# design.net
KiCad netlist of a schematic drawn in Altium Designer
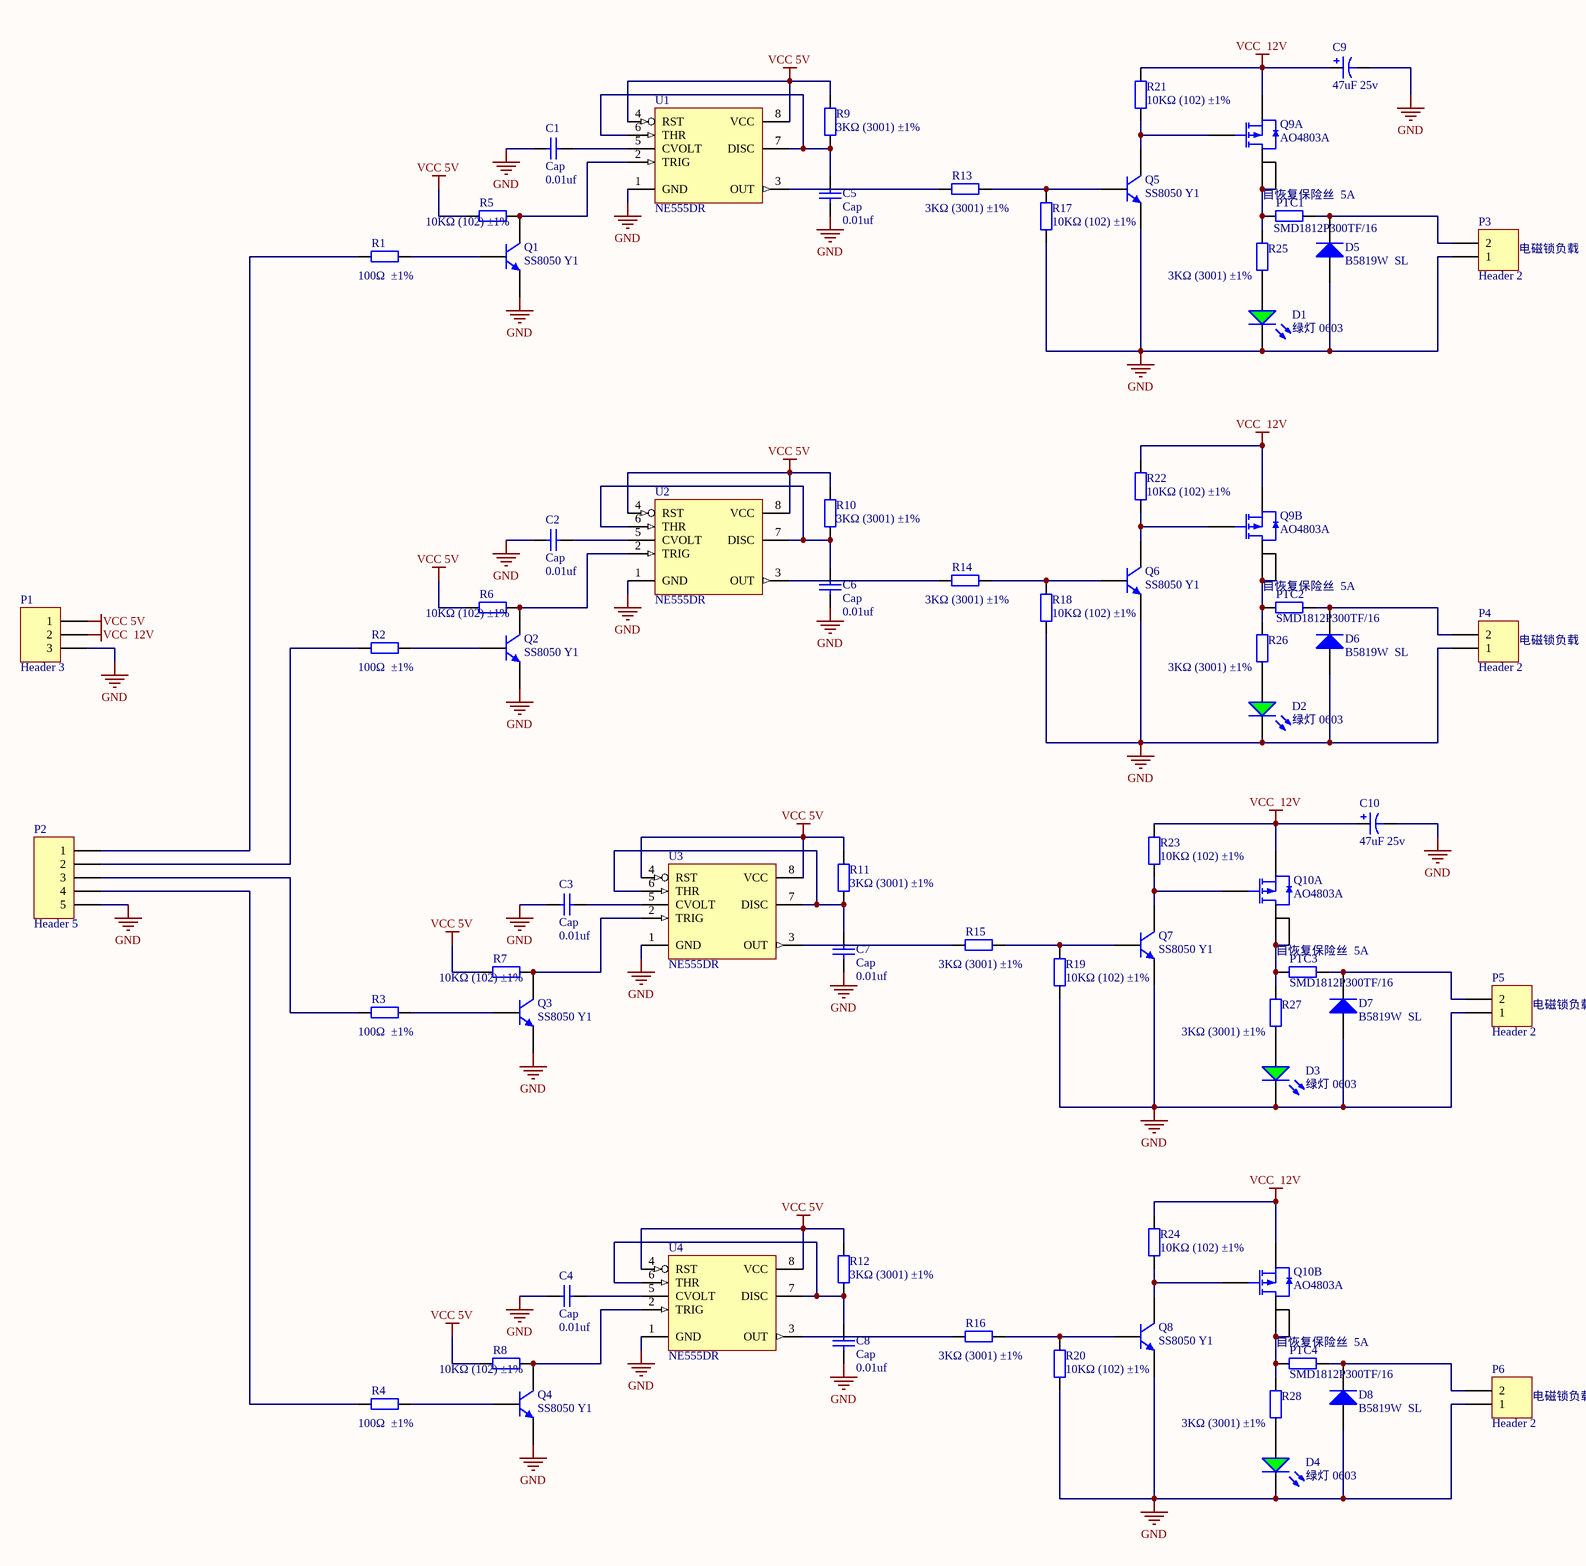
[diagram p0: 电磁阀驱动.SchDoc]

(export (version "E")
  (design (tool "Eeschema 10.0.6"))
  (components
    (comp (ref "C1")
      (value "Cap")
      (footprint "0603C")
      (description "Capacitor")
      (fields (field (name "ALTIUM_VALUE") "0.01uf") (field (name "PUBLISHER") "Altium Limited"))
      (libsource (lib "Miscellaneous Devices") (part "Cap"))
    )
    (comp (ref "C2")
      (value "Cap")
      (footprint "0603C")
      (description "Capacitor")
      (fields (field (name "ALTIUM_VALUE") "0.01uf") (field (name "PUBLISHER") "Altium Limited"))
      (libsource (lib "Miscellaneous Devices") (part "Cap"))
    )
    (comp (ref "C3")
      (value "Cap")
      (footprint "0603C")
      (description "Capacitor")
      (fields (field (name "ALTIUM_VALUE") "0.01uf") (field (name "PUBLISHER") "Altium Limited"))
      (libsource (lib "Miscellaneous Devices") (part "Cap"))
    )
    (comp (ref "C4")
      (value "Cap")
      (footprint "0603C")
      (description "Capacitor")
      (fields (field (name "ALTIUM_VALUE") "0.01uf") (field (name "PUBLISHER") "Altium Limited"))
      (libsource (lib "Miscellaneous Devices") (part "Cap"))
    )
    (comp (ref "C5")
      (value "Cap")
      (footprint "0603C")
      (description "Capacitor")
      (fields (field (name "ALTIUM_VALUE") "0.01uf") (field (name "PUBLISHER") "Altium Limited"))
      (libsource (lib "Miscellaneous Devices") (part "Cap"))
    )
    (comp (ref "C6")
      (value "Cap")
      (footprint "0603C")
      (description "Capacitor")
      (fields (field (name "ALTIUM_VALUE") "0.01uf") (field (name "PUBLISHER") "Altium Limited"))
      (libsource (lib "Miscellaneous Devices") (part "Cap"))
    )
    (comp (ref "C7")
      (value "Cap")
      (footprint "0603C")
      (description "Capacitor")
      (fields (field (name "ALTIUM_VALUE") "0.01uf") (field (name "PUBLISHER") "Altium Limited"))
      (libsource (lib "Miscellaneous Devices") (part "Cap"))
    )
    (comp (ref "C8")
      (value "Cap")
      (footprint "0603C")
      (description "Capacitor")
      (fields (field (name "ALTIUM_VALUE") "0.01uf") (field (name "PUBLISHER") "Altium Limited"))
      (libsource (lib "Miscellaneous Devices") (part "Cap"))
    )
    (comp (ref "C9")
      (value "47uF 25v")
      (footprint "CAP_SMD_6*7")
      (description "Polarized Capacitor (Radial)")
      (fields (field (name "PUBLISHER") "Altium Limited"))
      (libsource (lib "Miscellaneous Devices") (part "Cap Pol1"))
    )
    (comp (ref "C10")
      (value "47uF 25v")
      (footprint "CAP_SMD_6*7")
      (description "Polarized Capacitor (Radial)")
      (fields (field (name "PUBLISHER") "Altium Limited"))
      (libsource (lib "Miscellaneous Devices") (part "Cap Pol1"))
    )
    (comp (ref "D1")
      (value "绿灯 0603")
      (footprint "0603_LED_S1")
      (description "发光二极管")
      (libsource (lib "Miscellaneous Devices LC") (part "0603 绿灯"))
    )
    (comp (ref "D2")
      (value "绿灯 0603")
      (footprint "0603_LED_S1")
      (description "发光二极管")
      (libsource (lib "Miscellaneous Devices LC") (part "0603 绿灯"))
    )
    (comp (ref "D3")
      (value "绿灯 0603")
      (footprint "0603_LED_S1")
      (description "发光二极管")
      (libsource (lib "Miscellaneous Devices LC") (part "0603 绿灯"))
    )
    (comp (ref "D4")
      (value "绿灯 0603")
      (footprint "0603_LED_S1")
      (description "发光二极管")
      (libsource (lib "Miscellaneous Devices LC") (part "0603 绿灯"))
    )
    (comp (ref "D5")
      (value "B5819W  SL")
      (footprint "SOD-123")
      (description "肖特基二极管")
      (libsource (lib "Miscellaneous Devices LC") (part "SOD-123 B5819W  SL"))
    )
    (comp (ref "D6")
      (value "B5819W  SL")
      (footprint "SOD-123")
      (description "肖特基二极管")
      (libsource (lib "Miscellaneous Devices LC") (part "SOD-123 B5819W  SL"))
    )
    (comp (ref "D7")
      (value "B5819W  SL")
      (footprint "SOD-123")
      (description "肖特基二极管")
      (libsource (lib "Miscellaneous Devices LC") (part "SOD-123 B5819W  SL"))
    )
    (comp (ref "D8")
      (value "B5819W  SL")
      (footprint "SOD-123")
      (description "肖特基二极管")
      (libsource (lib "Miscellaneous Devices LC") (part "SOD-123 B5819W  SL"))
    )
    (comp (ref "P1")
      (value "Header 3")
      (footprint "sip-3")
      (description "Header, 3-Pin")
      (fields (field (name "PUBLISHER") "Altium Limited"))
      (libsource (lib "Miscellaneous Connectors") (part "Header 3"))
    )
    (comp (ref "P2")
      (value "Header 5")
      (footprint "SIP-5")
      (description "Header, 5-Pin")
      (fields (field (name "PUBLISHER") "Altium Limited"))
      (libsource (lib "Miscellaneous Connectors") (part "Header 5"))
    )
    (comp (ref "P3")
      (value "Header 2")
      (footprint "SIP-2")
      (description "Header, 2-Pin")
      (fields (field (name "PUBLISHER") "Altium Limited"))
      (libsource (lib "Miscellaneous Connectors") (part "Header 2"))
    )
    (comp (ref "P4")
      (value "Header 2")
      (footprint "SIP-2")
      (description "Header, 2-Pin")
      (fields (field (name "PUBLISHER") "Altium Limited"))
      (libsource (lib "Miscellaneous Connectors") (part "Header 2"))
    )
    (comp (ref "P5")
      (value "Header 2")
      (footprint "SIP-2")
      (description "Header, 2-Pin")
      (fields (field (name "PUBLISHER") "Altium Limited"))
      (libsource (lib "Miscellaneous Connectors") (part "Header 2"))
    )
    (comp (ref "P6")
      (value "Header 2")
      (footprint "SIP-2")
      (description "Header, 2-Pin")
      (fields (field (name "PUBLISHER") "Altium Limited"))
      (libsource (lib "Miscellaneous Connectors") (part "Header 2"))
    )
    (comp (ref "PTC1")
      (value "SMD1812P300TF/16")
      (footprint "1812")
      (description "贴片电阻")
      (libsource (lib "") (part "0603 3KΩ (3001) 1%_2"))
    )
    (comp (ref "PTC2")
      (value "SMD1812P300TF/16")
      (footprint "1812")
      (description "贴片电阻")
      (libsource (lib "") (part "0603 3KΩ (3001) 1%_2"))
    )
    (comp (ref "PTC3")
      (value "SMD1812P300TF/16")
      (footprint "1812")
      (description "贴片电阻")
      (libsource (lib "") (part "0603 3KΩ (3001) 1%_2"))
    )
    (comp (ref "PTC4")
      (value "SMD1812P300TF/16")
      (footprint "1812")
      (description "贴片电阻")
      (libsource (lib "") (part "0603 3KΩ (3001) 1%_2"))
    )
    (comp (ref "Q1")
      (value "SS8050 Y1")
      (footprint "SOT-23(SOT-23-3)")
      (description "三极管")
      (libsource (lib "Miscellaneous Devices LC") (part "SOT-23 SS8050 Y1"))
    )
    (comp (ref "Q2")
      (value "SS8050 Y1")
      (footprint "SOT-23(SOT-23-3)")
      (description "三极管")
      (libsource (lib "Miscellaneous Devices LC") (part "SOT-23 SS8050 Y1"))
    )
    (comp (ref "Q3")
      (value "SS8050 Y1")
      (footprint "SOT-23(SOT-23-3)")
      (description "三极管")
      (libsource (lib "Miscellaneous Devices LC") (part "SOT-23 SS8050 Y1"))
    )
    (comp (ref "Q4")
      (value "SS8050 Y1")
      (footprint "SOT-23(SOT-23-3)")
      (description "三极管")
      (libsource (lib "Miscellaneous Devices LC") (part "SOT-23 SS8050 Y1"))
    )
    (comp (ref "Q5")
      (value "SS8050 Y1")
      (footprint "SOT-23(SOT-23-3)")
      (description "三极管")
      (libsource (lib "Miscellaneous Devices LC") (part "SOT-23 SS8050 Y1"))
    )
    (comp (ref "Q6")
      (value "SS8050 Y1")
      (footprint "SOT-23(SOT-23-3)")
      (description "三极管")
      (libsource (lib "Miscellaneous Devices LC") (part "SOT-23 SS8050 Y1"))
    )
    (comp (ref "Q7")
      (value "SS8050 Y1")
      (footprint "SOT-23(SOT-23-3)")
      (description "三极管")
      (libsource (lib "Miscellaneous Devices LC") (part "SOT-23 SS8050 Y1"))
    )
    (comp (ref "Q8")
      (value "SS8050 Y1")
      (footprint "SOT-23(SOT-23-3)")
      (description "三极管")
      (libsource (lib "Miscellaneous Devices LC") (part "SOT-23 SS8050 Y1"))
    )
    (comp (ref "Q9")
      (value "AO4803A")
      (footprint "SOP-8_150mil")
      (description "MOS(场效应管)")
      (libsource (lib "Miscellaneous Devices LC") (part "APM4953KC-TRG"))
    )
    (comp (ref "Q10")
      (value "AO4803A")
      (footprint "SOP-8_150mil")
      (description "MOS(场效应管)")
      (libsource (lib "Miscellaneous Devices LC") (part "APM4953KC-TRG"))
    )
    (comp (ref "R1")
      (value "100Ω  ±1%")
      (footprint "0603_R")
      (description "贴片电阻")
      (libsource (lib "Miscellaneous Devices LC") (part "0603 3KΩ (3001) 1%"))
    )
    (comp (ref "R2")
      (value "100Ω  ±1%")
      (footprint "0603_R")
      (description "贴片电阻")
      (libsource (lib "Miscellaneous Devices LC") (part "0603 3KΩ (3001) 1%"))
    )
    (comp (ref "R3")
      (value "100Ω  ±1%")
      (footprint "0603_R")
      (description "贴片电阻")
      (libsource (lib "Miscellaneous Devices LC") (part "0603 3KΩ (3001) 1%"))
    )
    (comp (ref "R4")
      (value "100Ω  ±1%")
      (footprint "0603_R")
      (description "贴片电阻")
      (libsource (lib "Miscellaneous Devices LC") (part "0603 3KΩ (3001) 1%"))
    )
    (comp (ref "R5")
      (value "10KΩ (102) ±1%")
      (footprint "0603_R")
      (description "贴片电阻")
      (libsource (lib "Miscellaneous Devices LC") (part "0603 3KΩ (3001) 1%"))
    )
    (comp (ref "R6")
      (value "10KΩ (102) ±1%")
      (footprint "0603_R")
      (description "贴片电阻")
      (libsource (lib "Miscellaneous Devices LC") (part "0603 3KΩ (3001) 1%"))
    )
    (comp (ref "R7")
      (value "10KΩ (102) ±1%")
      (footprint "0603_R")
      (description "贴片电阻")
      (libsource (lib "Miscellaneous Devices LC") (part "0603 3KΩ (3001) 1%"))
    )
    (comp (ref "R8")
      (value "10KΩ (102) ±1%")
      (footprint "0603_R")
      (description "贴片电阻")
      (libsource (lib "Miscellaneous Devices LC") (part "0603 3KΩ (3001) 1%"))
    )
    (comp (ref "R9")
      (value "3KΩ (3001) ±1%")
      (footprint "0603_R")
      (description "贴片电阻")
      (libsource (lib "") (part "0603 3KΩ (3001) 1%_3"))
    )
    (comp (ref "R10")
      (value "3KΩ (3001) ±1%")
      (footprint "0603_R")
      (description "贴片电阻")
      (libsource (lib "") (part "0603 3KΩ (3001) 1%_3"))
    )
    (comp (ref "R11")
      (value "3KΩ (3001) ±1%")
      (footprint "0603_R")
      (description "贴片电阻")
      (libsource (lib "") (part "0603 3KΩ (3001) 1%_3"))
    )
    (comp (ref "R12")
      (value "3KΩ (3001) ±1%")
      (footprint "0603_R")
      (description "贴片电阻")
      (libsource (lib "") (part "0603 3KΩ (3001) 1%_3"))
    )
    (comp (ref "R13")
      (value "3KΩ (3001) ±1%")
      (footprint "0603_R")
      (description "贴片电阻")
      (libsource (lib "") (part "0603 3KΩ (3001) 1%_2"))
    )
    (comp (ref "R14")
      (value "3KΩ (3001) ±1%")
      (footprint "0603_R")
      (description "贴片电阻")
      (libsource (lib "") (part "0603 3KΩ (3001) 1%_2"))
    )
    (comp (ref "R15")
      (value "3KΩ (3001) ±1%")
      (footprint "0603_R")
      (description "贴片电阻")
      (libsource (lib "") (part "0603 3KΩ (3001) 1%_2"))
    )
    (comp (ref "R16")
      (value "3KΩ (3001) ±1%")
      (footprint "0603_R")
      (description "贴片电阻")
      (libsource (lib "") (part "0603 3KΩ (3001) 1%_2"))
    )
    (comp (ref "R17")
      (value "10KΩ (102) ±1%")
      (footprint "0603_R")
      (description "贴片电阻")
      (libsource (lib "") (part "0603 3KΩ (3001) 1%_1"))
    )
    (comp (ref "R18")
      (value "10KΩ (102) ±1%")
      (footprint "0603_R")
      (description "贴片电阻")
      (libsource (lib "") (part "0603 3KΩ (3001) 1%_1"))
    )
    (comp (ref "R19")
      (value "10KΩ (102) ±1%")
      (footprint "0603_R")
      (description "贴片电阻")
      (libsource (lib "") (part "0603 3KΩ (3001) 1%_1"))
    )
    (comp (ref "R20")
      (value "10KΩ (102) ±1%")
      (footprint "0603_R")
      (description "贴片电阻")
      (libsource (lib "") (part "0603 3KΩ (3001) 1%_1"))
    )
    (comp (ref "R21")
      (value "10KΩ (102) ±1%")
      (footprint "0603_R")
      (description "贴片电阻")
      (libsource (lib "") (part "0603 3KΩ (3001) 1%_1"))
    )
    (comp (ref "R22")
      (value "10KΩ (102) ±1%")
      (footprint "0603_R")
      (description "贴片电阻")
      (libsource (lib "") (part "0603 3KΩ (3001) 1%_1"))
    )
    (comp (ref "R23")
      (value "10KΩ (102) ±1%")
      (footprint "0603_R")
      (description "贴片电阻")
      (libsource (lib "") (part "0603 3KΩ (3001) 1%_1"))
    )
    (comp (ref "R24")
      (value "10KΩ (102) ±1%")
      (footprint "0603_R")
      (description "贴片电阻")
      (libsource (lib "") (part "0603 3KΩ (3001) 1%_1"))
    )
    (comp (ref "R25")
      (value "3KΩ (3001) ±1%")
      (footprint "0603_R")
      (description "贴片电阻")
      (libsource (lib "") (part "0603 3KΩ (3001) 1%_3"))
    )
    (comp (ref "R26")
      (value "3KΩ (3001) ±1%")
      (footprint "0603_R")
      (description "贴片电阻")
      (libsource (lib "") (part "0603 3KΩ (3001) 1%_3"))
    )
    (comp (ref "R27")
      (value "3KΩ (3001) ±1%")
      (footprint "0603_R")
      (description "贴片电阻")
      (libsource (lib "") (part "0603 3KΩ (3001) 1%_3"))
    )
    (comp (ref "R28")
      (value "3KΩ (3001) ±1%")
      (footprint "0603_R")
      (description "贴片电阻")
      (libsource (lib "") (part "0603 3KΩ (3001) 1%_3"))
    )
    (comp (ref "U1")
      (value "NE555DR")
      (footprint "SOIC-8_150mil")
      (description "时基集成")
      (libsource (lib "Miscellaneous Devices LC") (part "NE555DR_[C7593]"))
    )
    (comp (ref "U2")
      (value "NE555DR")
      (footprint "SOIC-8_150mil")
      (description "时基集成")
      (libsource (lib "Miscellaneous Devices LC") (part "NE555DR_[C7593]"))
    )
    (comp (ref "U3")
      (value "NE555DR")
      (footprint "SOIC-8_150mil")
      (description "时基集成")
      (libsource (lib "Miscellaneous Devices LC") (part "NE555DR_[C7593]"))
    )
    (comp (ref "U4")
      (value "NE555DR")
      (footprint "SOIC-8_150mil")
      (description "时基集成")
      (libsource (lib "Miscellaneous Devices LC") (part "NE555DR_[C7593]"))
    )
  )
  (nets
    (net (code "1") (name "GND") (class "Default")
      (node (ref "C1") (pin "1") (pinfunction "1_1") (pintype "passive"))
      (node (ref "C10") (pin "2") (pinfunction "2_2") (pintype "passive"))
      (node (ref "C2") (pin "1") (pinfunction "1_1") (pintype "passive"))
      (node (ref "C3") (pin "1") (pinfunction "1_1") (pintype "passive"))
      (node (ref "C4") (pin "1") (pinfunction "1_1") (pintype "passive"))
      (node (ref "C5") (pin "1") (pinfunction "1_1") (pintype "passive"))
      (node (ref "C6") (pin "1") (pinfunction "1_1") (pintype "passive"))
      (node (ref "C7") (pin "1") (pinfunction "1_1") (pintype "passive"))
      (node (ref "C8") (pin "1") (pinfunction "1_1") (pintype "passive"))
      (node (ref "C9") (pin "2") (pinfunction "2_2") (pintype "passive"))
      (node (ref "D1") (pin "K") (pinfunction "K_K") (pintype "passive"))
      (node (ref "D2") (pin "K") (pinfunction "K_K") (pintype "passive"))
      (node (ref "D3") (pin "K") (pinfunction "K_K") (pintype "passive"))
      (node (ref "D4") (pin "K") (pinfunction "K_K") (pintype "passive"))
      (node (ref "D5") (pin "1") (pinfunction "A_1") (pintype "passive"))
      (node (ref "D6") (pin "1") (pinfunction "A_1") (pintype "passive"))
      (node (ref "D7") (pin "1") (pinfunction "A_1") (pintype "passive"))
      (node (ref "D8") (pin "1") (pinfunction "A_1") (pintype "passive"))
      (node (ref "P1") (pin "3") (pinfunction "3_3") (pintype "passive"))
      (node (ref "P2") (pin "5") (pinfunction "5_5") (pintype "passive"))
      (node (ref "P3") (pin "1") (pinfunction "1_1") (pintype "passive"))
      (node (ref "P4") (pin "1") (pinfunction "1_1") (pintype "passive"))
      (node (ref "P5") (pin "1") (pinfunction "1_1") (pintype "passive"))
      (node (ref "P6") (pin "1") (pinfunction "1_1") (pintype "passive"))
      (node (ref "Q1") (pin "2") (pinfunction "E_2") (pintype "passive"))
      (node (ref "Q2") (pin "2") (pinfunction "E_2") (pintype "passive"))
      (node (ref "Q3") (pin "2") (pinfunction "E_2") (pintype "passive"))
      (node (ref "Q4") (pin "2") (pinfunction "E_2") (pintype "passive"))
      (node (ref "Q5") (pin "2") (pinfunction "E_2") (pintype "passive"))
      (node (ref "Q6") (pin "2") (pinfunction "E_2") (pintype "passive"))
      (node (ref "Q7") (pin "2") (pinfunction "E_2") (pintype "passive"))
      (node (ref "Q8") (pin "2") (pinfunction "E_2") (pintype "passive"))
      (node (ref "R17") (pin "1") (pinfunction "1_1") (pintype "passive"))
      (node (ref "R18") (pin "1") (pinfunction "1_1") (pintype "passive"))
      (node (ref "R19") (pin "1") (pinfunction "1_1") (pintype "passive"))
      (node (ref "R20") (pin "1") (pinfunction "1_1") (pintype "passive"))
      (node (ref "U1") (pin "1") (pinfunction "GND_1") (pintype "power_in"))
      (node (ref "U2") (pin "1") (pinfunction "GND_1") (pintype "power_in"))
      (node (ref "U3") (pin "1") (pinfunction "GND_1") (pintype "power_in"))
      (node (ref "U4") (pin "1") (pinfunction "GND_1") (pintype "power_in"))
    )
    (net (code "2") (name "Net-(D1-PadA)") (class "Default")
      (node (ref "D1") (pin "A") (pinfunction "A_A") (pintype "passive"))
      (node (ref "R25") (pin "2") (pinfunction "2_2") (pintype "passive"))
    )
    (net (code "3") (name "Net-(D2-PadA)") (class "Default")
      (node (ref "D2") (pin "A") (pinfunction "A_A") (pintype "passive"))
      (node (ref "R26") (pin "2") (pinfunction "2_2") (pintype "passive"))
    )
    (net (code "4") (name "Net-(D3-PadA)") (class "Default")
      (node (ref "D3") (pin "A") (pinfunction "A_A") (pintype "passive"))
      (node (ref "R27") (pin "2") (pinfunction "2_2") (pintype "passive"))
    )
    (net (code "5") (name "Net-(D4-PadA)") (class "Default")
      (node (ref "D4") (pin "A") (pinfunction "A_A") (pintype "passive"))
      (node (ref "R28") (pin "2") (pinfunction "2_2") (pintype "passive"))
    )
    (net (code "6") (name "Net-(D5-K)") (class "Default")
      (node (ref "D5") (pin "2") (pinfunction "K_2") (pintype "passive"))
      (node (ref "P3") (pin "2") (pinfunction "2_2") (pintype "passive"))
      (node (ref "PTC1") (pin "2") (pinfunction "2_2") (pintype "passive"))
    )
    (net (code "7") (name "Net-(D6-K)") (class "Default")
      (node (ref "D6") (pin "2") (pinfunction "K_2") (pintype "passive"))
      (node (ref "P4") (pin "2") (pinfunction "2_2") (pintype "passive"))
      (node (ref "PTC2") (pin "2") (pinfunction "2_2") (pintype "passive"))
    )
    (net (code "8") (name "Net-(D7-K)") (class "Default")
      (node (ref "D7") (pin "2") (pinfunction "K_2") (pintype "passive"))
      (node (ref "P5") (pin "2") (pinfunction "2_2") (pintype "passive"))
      (node (ref "PTC3") (pin "2") (pinfunction "2_2") (pintype "passive"))
    )
    (net (code "9") (name "Net-(D8-K)") (class "Default")
      (node (ref "D8") (pin "2") (pinfunction "K_2") (pintype "passive"))
      (node (ref "P6") (pin "2") (pinfunction "2_2") (pintype "passive"))
      (node (ref "PTC4") (pin "2") (pinfunction "2_2") (pintype "passive"))
    )
    (net (code "10") (name "Net-(P2-Pad1)") (class "Default")
      (node (ref "P2") (pin "1") (pinfunction "1_1") (pintype "passive"))
      (node (ref "R1") (pin "2") (pinfunction "2_2") (pintype "passive"))
    )
    (net (code "11") (name "Net-(P2-Pad2)") (class "Default")
      (node (ref "P2") (pin "2") (pinfunction "2_2") (pintype "passive"))
      (node (ref "R2") (pin "2") (pinfunction "2_2") (pintype "passive"))
    )
    (net (code "12") (name "Net-(P2-Pad3)") (class "Default")
      (node (ref "P2") (pin "3") (pinfunction "3_3") (pintype "passive"))
      (node (ref "R3") (pin "2") (pinfunction "2_2") (pintype "passive"))
    )
    (net (code "13") (name "Net-(P2-Pad4)") (class "Default")
      (node (ref "P2") (pin "4") (pinfunction "4_4") (pintype "passive"))
      (node (ref "R4") (pin "2") (pinfunction "2_2") (pintype "passive"))
    )
    (net (code "14") (name "Net-(PTC1-Pad1)") (class "Default")
      (node (ref "PTC1") (pin "1") (pinfunction "1_1") (pintype "passive"))
      (node (ref "Q9") (pin "7") (pinfunction "D_7") (pintype "passive"))
      (node (ref "Q9") (pin "8") (pinfunction "D_8") (pintype "passive"))
      (node (ref "R25") (pin "1") (pinfunction "1_1") (pintype "passive"))
    )
    (net (code "15") (name "Net-(PTC2-Pad1)") (class "Default")
      (node (ref "PTC2") (pin "1") (pinfunction "1_1") (pintype "passive"))
      (node (ref "Q9") (pin "5") (pinfunction "D_5") (pintype "passive"))
      (node (ref "Q9") (pin "6") (pinfunction "D_6") (pintype "passive"))
      (node (ref "R26") (pin "1") (pinfunction "1_1") (pintype "passive"))
    )
    (net (code "16") (name "Net-(PTC3-Pad1)") (class "Default")
      (node (ref "PTC3") (pin "1") (pinfunction "1_1") (pintype "passive"))
      (node (ref "Q10") (pin "7") (pinfunction "D_7") (pintype "passive"))
      (node (ref "Q10") (pin "8") (pinfunction "D_8") (pintype "passive"))
      (node (ref "R27") (pin "1") (pinfunction "1_1") (pintype "passive"))
    )
    (net (code "17") (name "Net-(PTC4-Pad1)") (class "Default")
      (node (ref "PTC4") (pin "1") (pinfunction "1_1") (pintype "passive"))
      (node (ref "Q10") (pin "5") (pinfunction "D_5") (pintype "passive"))
      (node (ref "Q10") (pin "6") (pinfunction "D_6") (pintype "passive"))
      (node (ref "R28") (pin "1") (pinfunction "1_1") (pintype "passive"))
    )
    (net (code "18") (name "Net-(Q1-B)") (class "Default")
      (node (ref "Q1") (pin "1") (pinfunction "B_1") (pintype "passive"))
      (node (ref "R1") (pin "1") (pinfunction "1_1") (pintype "passive"))
    )
    (net (code "19") (name "Net-(Q1-C)") (class "Default")
      (node (ref "Q1") (pin "3") (pinfunction "C_3") (pintype "passive"))
      (node (ref "R5") (pin "1") (pinfunction "1_1") (pintype "passive"))
      (node (ref "U1") (pin "2") (pinfunction "TRIG_2") (pintype "input"))
    )
    (net (code "20") (name "Net-(Q2-B)") (class "Default")
      (node (ref "Q2") (pin "1") (pinfunction "B_1") (pintype "passive"))
      (node (ref "R2") (pin "1") (pinfunction "1_1") (pintype "passive"))
    )
    (net (code "21") (name "Net-(Q2-C)") (class "Default")
      (node (ref "Q2") (pin "3") (pinfunction "C_3") (pintype "passive"))
      (node (ref "R6") (pin "1") (pinfunction "1_1") (pintype "passive"))
      (node (ref "U2") (pin "2") (pinfunction "TRIG_2") (pintype "input"))
    )
    (net (code "22") (name "Net-(Q3-B)") (class "Default")
      (node (ref "Q3") (pin "1") (pinfunction "B_1") (pintype "passive"))
      (node (ref "R3") (pin "1") (pinfunction "1_1") (pintype "passive"))
    )
    (net (code "23") (name "Net-(Q3-C)") (class "Default")
      (node (ref "Q3") (pin "3") (pinfunction "C_3") (pintype "passive"))
      (node (ref "R7") (pin "1") (pinfunction "1_1") (pintype "passive"))
      (node (ref "U3") (pin "2") (pinfunction "TRIG_2") (pintype "input"))
    )
    (net (code "24") (name "Net-(Q4-B)") (class "Default")
      (node (ref "Q4") (pin "1") (pinfunction "B_1") (pintype "passive"))
      (node (ref "R4") (pin "1") (pinfunction "1_1") (pintype "passive"))
    )
    (net (code "25") (name "Net-(Q4-C)") (class "Default")
      (node (ref "Q4") (pin "3") (pinfunction "C_3") (pintype "passive"))
      (node (ref "R8") (pin "1") (pinfunction "1_1") (pintype "passive"))
      (node (ref "U4") (pin "2") (pinfunction "TRIG_2") (pintype "input"))
    )
    (net (code "26") (name "Net-(Q5-B)") (class "Default")
      (node (ref "Q5") (pin "1") (pinfunction "B_1") (pintype "passive"))
      (node (ref "R13") (pin "2") (pinfunction "2_2") (pintype "passive"))
      (node (ref "R17") (pin "2") (pinfunction "2_2") (pintype "passive"))
    )
    (net (code "27") (name "Net-(Q5-C)") (class "Default")
      (node (ref "Q5") (pin "3") (pinfunction "C_3") (pintype "passive"))
      (node (ref "Q9") (pin "2") (pinfunction "G_2") (pintype "passive"))
      (node (ref "R21") (pin "1") (pinfunction "1_1") (pintype "passive"))
    )
    (net (code "28") (name "Net-(Q6-B)") (class "Default")
      (node (ref "Q6") (pin "1") (pinfunction "B_1") (pintype "passive"))
      (node (ref "R14") (pin "2") (pinfunction "2_2") (pintype "passive"))
      (node (ref "R18") (pin "2") (pinfunction "2_2") (pintype "passive"))
    )
    (net (code "29") (name "Net-(Q6-C)") (class "Default")
      (node (ref "Q6") (pin "3") (pinfunction "C_3") (pintype "passive"))
      (node (ref "Q9") (pin "4") (pinfunction "G_4") (pintype "passive"))
      (node (ref "R22") (pin "1") (pinfunction "1_1") (pintype "passive"))
    )
    (net (code "30") (name "Net-(Q7-B)") (class "Default")
      (node (ref "Q7") (pin "1") (pinfunction "B_1") (pintype "passive"))
      (node (ref "R15") (pin "2") (pinfunction "2_2") (pintype "passive"))
      (node (ref "R19") (pin "2") (pinfunction "2_2") (pintype "passive"))
    )
    (net (code "31") (name "Net-(Q8-B)") (class "Default")
      (node (ref "Q8") (pin "1") (pinfunction "B_1") (pintype "passive"))
      (node (ref "R16") (pin "2") (pinfunction "2_2") (pintype "passive"))
      (node (ref "R20") (pin "2") (pinfunction "2_2") (pintype "passive"))
    )
    (net (code "32") (name "Net-(Q10A-G)") (class "Default")
      (node (ref "Q10") (pin "2") (pinfunction "G_2") (pintype "passive"))
      (node (ref "Q7") (pin "3") (pinfunction "C_3") (pintype "passive"))
      (node (ref "R23") (pin "1") (pinfunction "1_1") (pintype "passive"))
    )
    (net (code "33") (name "Net-(Q10B-G)") (class "Default")
      (node (ref "Q10") (pin "4") (pinfunction "G_4") (pintype "passive"))
      (node (ref "Q8") (pin "3") (pinfunction "C_3") (pintype "passive"))
      (node (ref "R24") (pin "1") (pinfunction "1_1") (pintype "passive"))
    )
    (net (code "34") (name "Net-(U1-CVOLT)") (class "Default")
      (node (ref "C1") (pin "2") (pinfunction "2_2") (pintype "passive"))
      (node (ref "U1") (pin "5") (pinfunction "CVOLT_5") (pintype "passive"))
    )
    (net (code "35") (name "Net-(U1-DISC)") (class "Default")
      (node (ref "C5") (pin "2") (pinfunction "2_2") (pintype "passive"))
      (node (ref "R9") (pin "2") (pinfunction "2_2") (pintype "passive"))
      (node (ref "U1") (pin "6") (pinfunction "THR_6") (pintype "input"))
      (node (ref "U1") (pin "7") (pinfunction "DISC_7") (pintype "open_collector"))
    )
    (net (code "36") (name "Net-(U1-OUT)") (class "Default")
      (node (ref "R13") (pin "1") (pinfunction "1_1") (pintype "passive"))
      (node (ref "U1") (pin "3") (pinfunction "OUT_3") (pintype "output"))
    )
    (net (code "37") (name "Net-(U2-CVOLT)") (class "Default")
      (node (ref "C2") (pin "2") (pinfunction "2_2") (pintype "passive"))
      (node (ref "U2") (pin "5") (pinfunction "CVOLT_5") (pintype "passive"))
    )
    (net (code "38") (name "Net-(U2-DISC)") (class "Default")
      (node (ref "C6") (pin "2") (pinfunction "2_2") (pintype "passive"))
      (node (ref "R10") (pin "2") (pinfunction "2_2") (pintype "passive"))
      (node (ref "U2") (pin "6") (pinfunction "THR_6") (pintype "input"))
      (node (ref "U2") (pin "7") (pinfunction "DISC_7") (pintype "open_collector"))
    )
    (net (code "39") (name "Net-(U2-OUT)") (class "Default")
      (node (ref "R14") (pin "1") (pinfunction "1_1") (pintype "passive"))
      (node (ref "U2") (pin "3") (pinfunction "OUT_3") (pintype "output"))
    )
    (net (code "40") (name "Net-(U3-CVOLT)") (class "Default")
      (node (ref "C3") (pin "2") (pinfunction "2_2") (pintype "passive"))
      (node (ref "U3") (pin "5") (pinfunction "CVOLT_5") (pintype "passive"))
    )
    (net (code "41") (name "Net-(U3-DISC)") (class "Default")
      (node (ref "C7") (pin "2") (pinfunction "2_2") (pintype "passive"))
      (node (ref "R11") (pin "2") (pinfunction "2_2") (pintype "passive"))
      (node (ref "U3") (pin "6") (pinfunction "THR_6") (pintype "input"))
      (node (ref "U3") (pin "7") (pinfunction "DISC_7") (pintype "open_collector"))
    )
    (net (code "42") (name "Net-(U3-OUT)") (class "Default")
      (node (ref "R15") (pin "1") (pinfunction "1_1") (pintype "passive"))
      (node (ref "U3") (pin "3") (pinfunction "OUT_3") (pintype "output"))
    )
    (net (code "43") (name "Net-(U4-CVOLT)") (class "Default")
      (node (ref "C4") (pin "2") (pinfunction "2_2") (pintype "passive"))
      (node (ref "U4") (pin "5") (pinfunction "CVOLT_5") (pintype "passive"))
    )
    (net (code "44") (name "Net-(U4-DISC)") (class "Default")
      (node (ref "C8") (pin "2") (pinfunction "2_2") (pintype "passive"))
      (node (ref "R12") (pin "2") (pinfunction "2_2") (pintype "passive"))
      (node (ref "U4") (pin "6") (pinfunction "THR_6") (pintype "input"))
      (node (ref "U4") (pin "7") (pinfunction "DISC_7") (pintype "open_collector"))
    )
    (net (code "45") (name "Net-(U4-OUT)") (class "Default")
      (node (ref "R16") (pin "1") (pinfunction "1_1") (pintype "passive"))
      (node (ref "U4") (pin "3") (pinfunction "OUT_3") (pintype "output"))
    )
    (net (code "46") (name "VCC  12V") (class "Default")
      (node (ref "C10") (pin "1") (pinfunction "1_1") (pintype "passive"))
      (node (ref "C9") (pin "1") (pinfunction "1_1") (pintype "passive"))
      (node (ref "P1") (pin "2") (pinfunction "2_2") (pintype "passive"))
      (node (ref "Q10") (pin "1") (pinfunction "S_1") (pintype "passive"))
      (node (ref "Q10") (pin "3") (pinfunction "S_3") (pintype "passive"))
      (node (ref "Q9") (pin "1") (pinfunction "S_1") (pintype "passive"))
      (node (ref "Q9") (pin "3") (pinfunction "S_3") (pintype "passive"))
      (node (ref "R21") (pin "2") (pinfunction "2_2") (pintype "passive"))
      (node (ref "R22") (pin "2") (pinfunction "2_2") (pintype "passive"))
      (node (ref "R23") (pin "2") (pinfunction "2_2") (pintype "passive"))
      (node (ref "R24") (pin "2") (pinfunction "2_2") (pintype "passive"))
    )
    (net (code "47") (name "VCC 5V") (class "Default")
      (node (ref "P1") (pin "1") (pinfunction "1_1") (pintype "passive"))
      (node (ref "R10") (pin "1") (pinfunction "1_1") (pintype "passive"))
      (node (ref "R11") (pin "1") (pinfunction "1_1") (pintype "passive"))
      (node (ref "R12") (pin "1") (pinfunction "1_1") (pintype "passive"))
      (node (ref "R5") (pin "2") (pinfunction "2_2") (pintype "passive"))
      (node (ref "R6") (pin "2") (pinfunction "2_2") (pintype "passive"))
      (node (ref "R7") (pin "2") (pinfunction "2_2") (pintype "passive"))
      (node (ref "R8") (pin "2") (pinfunction "2_2") (pintype "passive"))
      (node (ref "R9") (pin "1") (pinfunction "1_1") (pintype "passive"))
      (node (ref "U1") (pin "4") (pinfunction "RST_4") (pintype "input"))
      (node (ref "U1") (pin "8") (pinfunction "VCC_8") (pintype "power_in"))
      (node (ref "U2") (pin "4") (pinfunction "RST_4") (pintype "input"))
      (node (ref "U2") (pin "8") (pinfunction "VCC_8") (pintype "power_in"))
      (node (ref "U3") (pin "4") (pinfunction "RST_4") (pintype "input"))
      (node (ref "U3") (pin "8") (pinfunction "VCC_8") (pintype "power_in"))
      (node (ref "U4") (pin "4") (pinfunction "RST_4") (pintype "input"))
      (node (ref "U4") (pin "8") (pinfunction "VCC_8") (pintype "power_in"))
    )
  )
)
